# Payload_PC104.net
KiCad netlist of a schematic drawn in Altium Designer
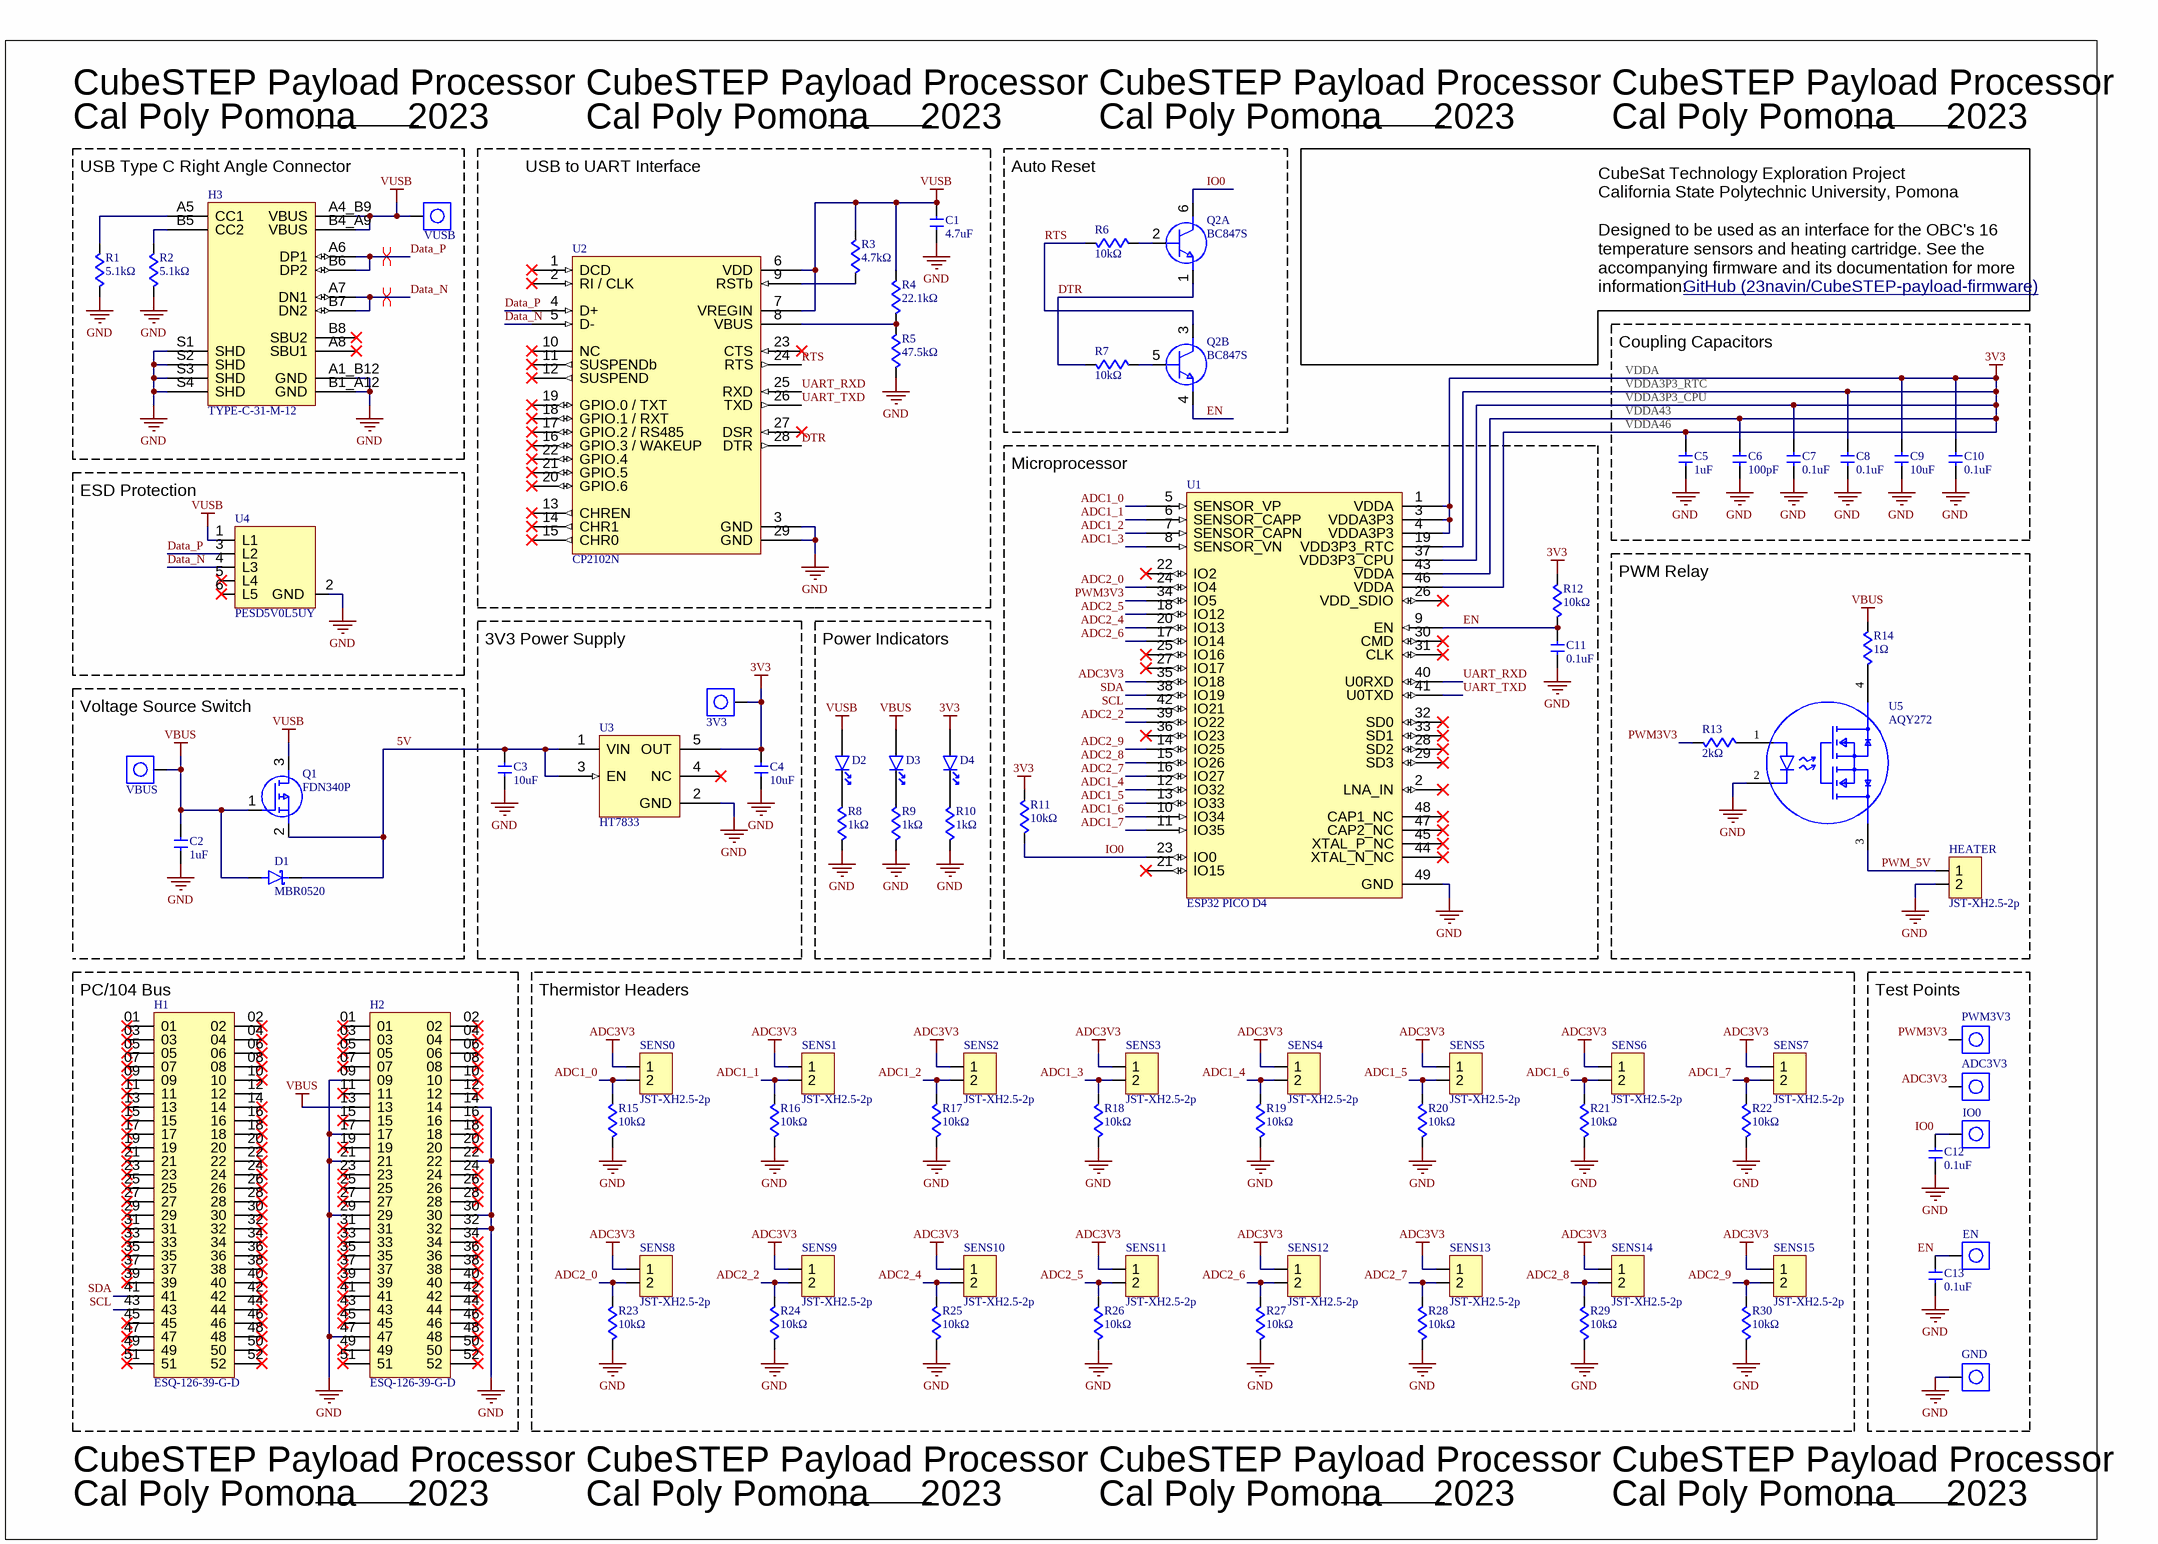
[diagram p0: Payload PC104.SchDoc]

(export (version "E")
  (design (tool "Eeschema 10.0.6"))
  (components
    (comp (ref "3V3")
      (value "Test Point")
      (footprint "Test Point-Footprint-1")
      (description "Signal test point")
      (libsource (lib "CubeSTEP Payload") (part "Test Point-Symbol-1"))
    )
    (comp (ref "ADC3V3")
      (value "Test Point")
      (footprint "Test Point-Footprint-1")
      (description "Signal test point")
      (libsource (lib "CubeSTEP Payload") (part "Test Point-Symbol-1"))
    )
    (comp (ref "C1")
      (value "4.7uF")
      (footprint "0402_Capacitor")
      (description "±20% 16V X5R SMD 0402")
      (fields (field (name "PART NUMBER") "CM05X5R475M16AH") (field (name "MANUFACTURER") "--"))
      (libsource (lib "CubeSTEP Payload") (part "Capacitor"))
    )
    (comp (ref "C2")
      (value "1uF")
      (footprint "0402_Capacitor")
      (description "±10% 16V X5R SMD 0402")
      (fields (field (name "PART NUMBER") "GRM155R61C105KA12D") (field (name "JLCPCB PART #") "C77006"))
      (libsource (lib "CubeSTEP Payload") (part "Capacitor"))
    )
    (comp (ref "C3")
      (value "10uF")
      (footprint "0805_Capacitor_Murata")
      (description "±10% 16V B SMD 0805")
      (fields (field (name "PART NUMBER") "GRM21BB31C106KE15L") (field (name "JLCPCB PART #") "C162317"))
      (libsource (lib "CubeSTEP Payload") (part "Capacitor"))
    )
    (comp (ref "C4")
      (value "10uF")
      (footprint "0805_Capacitor_Murata")
      (description "±10% 16V B SMD 0805")
      (fields (field (name "PART NUMBER") "GRM21BB31C106KE15L") (field (name "JLCPCB PART #") "C162317"))
      (libsource (lib "CubeSTEP Payload") (part "Capacitor"))
    )
    (comp (ref "C5")
      (value "1uF")
      (footprint "0402_Capacitor")
      (description "±10% 16V X5R SMD 0402")
      (fields (field (name "PART NUMBER") "GRM155R61C105KA12D") (field (name "JLCPCB PART #") "C77006"))
      (libsource (lib "CubeSTEP Payload") (part "Capacitor"))
    )
    (comp (ref "C6")
      (value "100pF")
      (footprint "0402_Capacitor")
      (description "±10% 16V X5R SMD 0402")
      (fields (field (name "MANUFACTURER") "YAGEO") (field (name "TOLERANCE") "±10%"))
      (libsource (lib "CubeSTEP Payload") (part "Capacitor"))
    )
    (comp (ref "C7")
      (value "0.1uF")
      (footprint "0402_Capacitor")
      (description "±20% 16V X5R SMD 0402")
      (fields (field (name "PART NUMBER") "TCC0402X5R104M160AT") (field (name "TOLERANCE") "±20%"))
      (libsource (lib "CubeSTEP Payload") (part "Capacitor"))
    )
    (comp (ref "C8")
      (value "0.1uF")
      (footprint "0402_Capacitor")
      (description "±20% 16V X5R SMD 0402")
      (fields (field (name "PART NUMBER") "TCC0402X5R104M160AT") (field (name "TOLERANCE") "±20%"))
      (libsource (lib "CubeSTEP Payload") (part "Capacitor"))
    )
    (comp (ref "C9")
      (value "10uF")
      (footprint "0805_Capacitor_Murata")
      (description "±10% 16V B SMD 0805")
      (fields (field (name "PART NUMBER") "GRM21BB31C106KE15L") (field (name "JLCPCB PART #") "C162317"))
      (libsource (lib "CubeSTEP Payload") (part "Capacitor"))
    )
    (comp (ref "C10")
      (value "0.1uF")
      (footprint "0402_Capacitor")
      (description "±20% 16V X5R SMD 0402")
      (fields (field (name "PART NUMBER") "TCC0402X5R104M160AT") (field (name "TOLERANCE") "±20%"))
      (libsource (lib "CubeSTEP Payload") (part "Capacitor"))
    )
    (comp (ref "C11")
      (value "0.1uF")
      (footprint "0402_Capacitor")
      (description "±20% 16V X5R SMD 0402")
      (fields (field (name "PART NUMBER") "TCC0402X5R104M160AT") (field (name "TOLERANCE") "±20%"))
      (libsource (lib "CubeSTEP Payload") (part "Capacitor"))
    )
    (comp (ref "C12")
      (value "0.1uF")
      (footprint "0402_Capacitor")
      (description "±20% 16V X5R SMD 0402")
      (fields (field (name "PART NUMBER") "TCC0402X5R104M160AT") (field (name "TOLERANCE") "±20%"))
      (libsource (lib "CubeSTEP Payload") (part "Capacitor"))
    )
    (comp (ref "C13")
      (value "0.1uF")
      (footprint "0402_Capacitor")
      (description "±20% 16V X5R SMD 0402")
      (fields (field (name "PART NUMBER") "TCC0402X5R104M160AT") (field (name "TOLERANCE") "±20%"))
      (libsource (lib "CubeSTEP Payload") (part "Capacitor"))
    )
    (comp (ref "D1")
      (value "MBR0520")
      (footprint "SOD-123_Diode_Onsemi")
      (description "Rectifier Diode, Schottky, 1 Phase, 1 Element, 0.5A, 20V V(RRM), Silicon")
      (fields (field (name "JLCPCB PART #") "C475717"))
      (libsource (lib "CubeSTEP Payload") (part "Schottky Diodde"))
    )
    (comp (ref "D2")
      (value "NCD0603R2")
      (footprint "0603_LED")
      (fields (field (name "JLCPCB PART #") "C90692"))
      (libsource (lib "CubeSTEP Payload") (part "LED"))
    )
    (comp (ref "D3")
      (value "NCD0603R2")
      (footprint "0603_LED")
      (fields (field (name "JLCPCB PART #") "C90692"))
      (libsource (lib "CubeSTEP Payload") (part "LED"))
    )
    (comp (ref "D4")
      (value "NCD0603R2")
      (footprint "0603_LED")
      (fields (field (name "JLCPCB PART #") "C90692"))
      (libsource (lib "CubeSTEP Payload") (part "LED"))
    )
    (comp (ref "EN")
      (value "Test Point")
      (footprint "Test Point-Footprint-1")
      (description "Signal test point")
      (libsource (lib "CubeSTEP Payload") (part "Test Point-Symbol-1"))
    )
    (comp (ref "GND")
      (value "Test Point")
      (footprint "Test Point-Footprint-1")
      (description "Signal test point")
      (libsource (lib "CubeSTEP Payload") (part "Test Point-Symbol-1"))
    )
    (comp (ref "H1")
      (value "ESQ-126-39-G-D")
      (footprint "ESQ-126-39-G-D")
      (libsource (lib "CubeSTEP Payload") (part "ESQ-126-39-G-D"))
    )
    (comp (ref "H2")
      (value "ESQ-126-39-G-D")
      (footprint "ESQ-126-39-G-D")
      (libsource (lib "CubeSTEP Payload") (part "ESQ-126-39-G-D"))
    )
    (comp (ref "H3")
      (value "TYPE-C-31-M-12")
      (footprint "TYPE-C-31-M-12-Footprint-1")
      (description "5A 1 16P Female Type-C SMD USB Connectors ROHS")
      (fields (field (name "JLCPCB PART #") "C165948"))
      (libsource (lib "CubeSTEP Payload") (part "TYPE-C-31-M-12-Symbol-1"))
    )
    (comp (ref "HEATER")
      (value "JST-XH2.5-2p")
      (footprint "2.5_2p_Header")
      (description "1x2P XH 1 2.5mm 2 Brass Push-Pull,P=2.5mm Wire To Board / Wire To Wire Connector ROHS")
      (fields
        (field (name "MANUFACTURER") "Ckmtw(Shenzhen Cankemeng)")
        (field (name "JLCPCB PART #") "C132479")
      )
      (libsource (lib "CubeSTEP Payload") (part "JST-XH2.5-2p"))
    )
    (comp (ref "IO0")
      (value "Test Point")
      (footprint "Test Point-Footprint-1")
      (description "Signal test point")
      (libsource (lib "CubeSTEP Payload") (part "Test Point-Symbol-1"))
    )
    (comp (ref "PWM3V3")
      (value "Test Point")
      (footprint "Test Point-Footprint-1")
      (description "Signal test point")
      (libsource (lib "CubeSTEP Payload") (part "Test Point-Symbol-1"))
    )
    (comp (ref "Q1")
      (value "FDN340P")
      (footprint "SOT-23")
      (description "SOT-23 MOSFETs ROHS")
      (fields (field (name "JLCPCB PART #") "C347510"))
      (libsource (lib "CubeSTEP Payload") (part "FDN340P"))
    )
    (comp (ref "Q2")
      (value "BC847S")
      (footprint "SC-70-6(SOT-363)")
      (description "Small Signal Bipolar Transistor, 0.1A I(C), 45V V(BR)CEO, 2-Element, NPN, Silicon")
      (fields (field (name "JLCPCB PART #") "C148112"))
      (libsource (lib "CubeSTEP Payload") (part "BC847S"))
    )
    (comp (ref "R1")
      (value "5.1kΩ")
      (footprint "0402_Resistor")
      (description "±0.5% 62.5mW 50V SMD 0402")
      (fields (field (name "POWER") "62.5mW") (field (name "PART NUMBER") "0402WGD5101TCE"))
      (libsource (lib "CubeSTEP Payload") (part "Resistor"))
    )
    (comp (ref "R2")
      (value "5.1kΩ")
      (footprint "0402_Resistor")
      (description "±0.5% 62.5mW 50V SMD 0402")
      (fields (field (name "POWER") "62.5mW") (field (name "PART NUMBER") "0402WGD5101TCE"))
      (libsource (lib "CubeSTEP Payload") (part "Resistor"))
    )
    (comp (ref "R3")
      (value "4.7kΩ")
      (footprint "0402_Resistor")
      (description "±1% 62.5mW 50V SMD 0402")
      (fields (field (name "PART NUMBER") "RC0402FR-074K7L") (field (name "POWER") "62.5mW"))
      (libsource (lib "CubeSTEP Payload") (part "Resistor"))
    )
    (comp (ref "R4")
      (value "22.1kΩ")
      (footprint "0402_Resistor")
      (description "±1% 62.5mW50V SMD 0402")
      (fields (field (name "POWER") "62.5mW") (field (name "PART NUMBER") "RC0402FR-0722K1L"))
      (libsource (lib "CubeSTEP Payload") (part "Resistor"))
    )
    (comp (ref "R5")
      (value "47.5kΩ")
      (footprint "0402_Resistor")
      (description "±1% 62.5mW 50V SMD 0402")
      (fields (field (name "PART NUMBER") "RC0402FR-0747K5L") (field (name "POWER") "62.5mW"))
      (libsource (lib "CubeSTEP Payload") (part "Resistor"))
    )
    (comp (ref "R6")
      (value "10kΩ")
      (footprint "0402_Resistor")
      (description "±1% 62.5mW 50V SMD 0402")
      (fields (field (name "POWER") "62.5mW") (field (name "TOLERANCE") "±1%"))
      (libsource (lib "CubeSTEP Payload") (part "Resistor"))
    )
    (comp (ref "R7")
      (value "10kΩ")
      (footprint "0402_Resistor")
      (description "±1% 62.5mW 50V SMD 0402")
      (fields (field (name "POWER") "62.5mW") (field (name "TOLERANCE") "±1%"))
      (libsource (lib "CubeSTEP Payload") (part "Resistor"))
    )
    (comp (ref "R8")
      (value "1kΩ")
      (footprint "0402_Resistor")
      (description "±1% 62.5mW 50V SMD 0402")
      (fields (field (name "JLCPCB PART #") "C106235") (field (name "TOLERANCE") "±1%"))
      (libsource (lib "CubeSTEP Payload") (part "Resistor"))
    )
    (comp (ref "R9")
      (value "1kΩ")
      (footprint "0402_Resistor")
      (description "±1% 62.5mW 50V SMD 0402")
      (fields (field (name "JLCPCB PART #") "C106235") (field (name "TOLERANCE") "±1%"))
      (libsource (lib "CubeSTEP Payload") (part "Resistor"))
    )
    (comp (ref "R10")
      (value "1kΩ")
      (footprint "0402_Resistor")
      (description "±1% 62.5mW 50V SMD 0402")
      (fields (field (name "JLCPCB PART #") "C106235") (field (name "TOLERANCE") "±1%"))
      (libsource (lib "CubeSTEP Payload") (part "Resistor"))
    )
    (comp (ref "R11")
      (value "10kΩ")
      (footprint "0402_Resistor")
      (description "±1% 62.5mW 50V SMD 0402")
      (fields (field (name "POWER") "62.5mW") (field (name "TOLERANCE") "±1%"))
      (libsource (lib "CubeSTEP Payload") (part "Resistor"))
    )
    (comp (ref "R12")
      (value "10kΩ")
      (footprint "0402_Resistor")
      (description "±1% 62.5mW 50V SMD 0402")
      (fields (field (name "POWER") "62.5mW") (field (name "TOLERANCE") "±1%"))
      (libsource (lib "CubeSTEP Payload") (part "Resistor"))
    )
    (comp (ref "R13")
      (value "2kΩ")
      (footprint "0402_Resistor")
      (description "±1% 62.5mW 50V SMD 0402")
      (fields (field (name "TOLERANCE") "±1%") (field (name "JLCPCB PART #") "C100291"))
      (libsource (lib "CubeSTEP Payload") (part "Resistor"))
    )
    (comp (ref "R14")
      (value "1Ω")
      (footprint "2010_Resistor")
      (description "±5% 0.75W 200V SMD 2010")
      (fields (field (name "POWER") "750mW") (field (name "TOLERANCE") "±5%"))
      (libsource (lib "CubeSTEP Payload") (part "Resistor"))
    )
    (comp (ref "R15")
      (value "10kΩ")
      (footprint "0402_Resistor")
      (description "±1% 62.5mW 50V SMD 0402")
      (fields (field (name "POWER") "62.5mW") (field (name "TOLERANCE") "±1%"))
      (libsource (lib "CubeSTEP Payload") (part "Resistor"))
    )
    (comp (ref "R16")
      (value "10kΩ")
      (footprint "0402_Resistor")
      (description "±1% 62.5mW 50V SMD 0402")
      (fields (field (name "POWER") "62.5mW") (field (name "TOLERANCE") "±1%"))
      (libsource (lib "CubeSTEP Payload") (part "Resistor"))
    )
    (comp (ref "R17")
      (value "10kΩ")
      (footprint "0402_Resistor")
      (description "±1% 62.5mW 50V SMD 0402")
      (fields (field (name "POWER") "62.5mW") (field (name "TOLERANCE") "±1%"))
      (libsource (lib "CubeSTEP Payload") (part "Resistor"))
    )
    (comp (ref "R18")
      (value "10kΩ")
      (footprint "0402_Resistor")
      (description "±1% 62.5mW 50V SMD 0402")
      (fields (field (name "POWER") "62.5mW") (field (name "TOLERANCE") "±1%"))
      (libsource (lib "CubeSTEP Payload") (part "Resistor"))
    )
    (comp (ref "R19")
      (value "10kΩ")
      (footprint "0402_Resistor")
      (description "±1% 62.5mW 50V SMD 0402")
      (fields (field (name "POWER") "62.5mW") (field (name "TOLERANCE") "±1%"))
      (libsource (lib "CubeSTEP Payload") (part "Resistor"))
    )
    (comp (ref "R20")
      (value "10kΩ")
      (footprint "0402_Resistor")
      (description "±1% 62.5mW 50V SMD 0402")
      (fields (field (name "POWER") "62.5mW") (field (name "TOLERANCE") "±1%"))
      (libsource (lib "CubeSTEP Payload") (part "Resistor"))
    )
    (comp (ref "R21")
      (value "10kΩ")
      (footprint "0402_Resistor")
      (description "±1% 62.5mW 50V SMD 0402")
      (fields (field (name "POWER") "62.5mW") (field (name "TOLERANCE") "±1%"))
      (libsource (lib "CubeSTEP Payload") (part "Resistor"))
    )
    (comp (ref "R22")
      (value "10kΩ")
      (footprint "0402_Resistor")
      (description "±1% 62.5mW 50V SMD 0402")
      (fields (field (name "POWER") "62.5mW") (field (name "TOLERANCE") "±1%"))
      (libsource (lib "CubeSTEP Payload") (part "Resistor"))
    )
    (comp (ref "R23")
      (value "10kΩ")
      (footprint "0402_Resistor")
      (description "±1% 62.5mW 50V SMD 0402")
      (fields (field (name "POWER") "62.5mW") (field (name "TOLERANCE") "±1%"))
      (libsource (lib "CubeSTEP Payload") (part "Resistor"))
    )
    (comp (ref "R24")
      (value "10kΩ")
      (footprint "0402_Resistor")
      (description "±1% 62.5mW 50V SMD 0402")
      (fields (field (name "POWER") "62.5mW") (field (name "TOLERANCE") "±1%"))
      (libsource (lib "CubeSTEP Payload") (part "Resistor"))
    )
    (comp (ref "R25")
      (value "10kΩ")
      (footprint "0402_Resistor")
      (description "±1% 62.5mW 50V SMD 0402")
      (fields (field (name "POWER") "62.5mW") (field (name "TOLERANCE") "±1%"))
      (libsource (lib "CubeSTEP Payload") (part "Resistor"))
    )
    (comp (ref "R26")
      (value "10kΩ")
      (footprint "0402_Resistor")
      (description "±1% 62.5mW 50V SMD 0402")
      (fields (field (name "POWER") "62.5mW") (field (name "TOLERANCE") "±1%"))
      (libsource (lib "CubeSTEP Payload") (part "Resistor"))
    )
    (comp (ref "R27")
      (value "10kΩ")
      (footprint "0402_Resistor")
      (description "±1% 62.5mW 50V SMD 0402")
      (fields (field (name "POWER") "62.5mW") (field (name "TOLERANCE") "±1%"))
      (libsource (lib "CubeSTEP Payload") (part "Resistor"))
    )
    (comp (ref "R28")
      (value "10kΩ")
      (footprint "0402_Resistor")
      (description "±1% 62.5mW 50V SMD 0402")
      (fields (field (name "POWER") "62.5mW") (field (name "TOLERANCE") "±1%"))
      (libsource (lib "CubeSTEP Payload") (part "Resistor"))
    )
    (comp (ref "R29")
      (value "10kΩ")
      (footprint "0402_Resistor")
      (description "±1% 62.5mW 50V SMD 0402")
      (fields (field (name "POWER") "62.5mW") (field (name "TOLERANCE") "±1%"))
      (libsource (lib "CubeSTEP Payload") (part "Resistor"))
    )
    (comp (ref "R30")
      (value "10kΩ")
      (footprint "0402_Resistor")
      (description "±1% 62.5mW 50V SMD 0402")
      (fields (field (name "POWER") "62.5mW") (field (name "TOLERANCE") "±1%"))
      (libsource (lib "CubeSTEP Payload") (part "Resistor"))
    )
    (comp (ref "SENS0")
      (value "JST-XH2.5-2p")
      (footprint "2.5_2p_Header")
      (description "1x2P XH 1 2.5mm 2 Brass Push-Pull,P=2.5mm Wire To Board / Wire To Wire Connector ROHS")
      (fields
        (field (name "MANUFACTURER") "Ckmtw(Shenzhen Cankemeng)")
        (field (name "JLCPCB PART #") "C132479")
      )
      (libsource (lib "CubeSTEP Payload") (part "JST-XH2.5-2p"))
    )
    (comp (ref "SENS1")
      (value "JST-XH2.5-2p")
      (footprint "2.5_2p_Header")
      (description "1x2P XH 1 2.5mm 2 Brass Push-Pull,P=2.5mm Wire To Board / Wire To Wire Connector ROHS")
      (fields
        (field (name "MANUFACTURER") "Ckmtw(Shenzhen Cankemeng)")
        (field (name "JLCPCB PART #") "C132479")
      )
      (libsource (lib "CubeSTEP Payload") (part "JST-XH2.5-2p"))
    )
    (comp (ref "SENS2")
      (value "JST-XH2.5-2p")
      (footprint "2.5_2p_Header")
      (description "1x2P XH 1 2.5mm 2 Brass Push-Pull,P=2.5mm Wire To Board / Wire To Wire Connector ROHS")
      (fields
        (field (name "MANUFACTURER") "Ckmtw(Shenzhen Cankemeng)")
        (field (name "JLCPCB PART #") "C132479")
      )
      (libsource (lib "CubeSTEP Payload") (part "JST-XH2.5-2p"))
    )
    (comp (ref "SENS3")
      (value "JST-XH2.5-2p")
      (footprint "2.5_2p_Header")
      (description "1x2P XH 1 2.5mm 2 Brass Push-Pull,P=2.5mm Wire To Board / Wire To Wire Connector ROHS")
      (fields
        (field (name "MANUFACTURER") "Ckmtw(Shenzhen Cankemeng)")
        (field (name "JLCPCB PART #") "C132479")
      )
      (libsource (lib "CubeSTEP Payload") (part "JST-XH2.5-2p"))
    )
    (comp (ref "SENS4")
      (value "JST-XH2.5-2p")
      (footprint "2.5_2p_Header")
      (description "1x2P XH 1 2.5mm 2 Brass Push-Pull,P=2.5mm Wire To Board / Wire To Wire Connector ROHS")
      (fields
        (field (name "MANUFACTURER") "Ckmtw(Shenzhen Cankemeng)")
        (field (name "JLCPCB PART #") "C132479")
      )
      (libsource (lib "CubeSTEP Payload") (part "JST-XH2.5-2p"))
    )
    (comp (ref "SENS5")
      (value "JST-XH2.5-2p")
      (footprint "2.5_2p_Header")
      (description "1x2P XH 1 2.5mm 2 Brass Push-Pull,P=2.5mm Wire To Board / Wire To Wire Connector ROHS")
      (fields
        (field (name "MANUFACTURER") "Ckmtw(Shenzhen Cankemeng)")
        (field (name "JLCPCB PART #") "C132479")
      )
      (libsource (lib "CubeSTEP Payload") (part "JST-XH2.5-2p"))
    )
    (comp (ref "SENS6")
      (value "JST-XH2.5-2p")
      (footprint "2.5_2p_Header")
      (description "1x2P XH 1 2.5mm 2 Brass Push-Pull,P=2.5mm Wire To Board / Wire To Wire Connector ROHS")
      (fields
        (field (name "MANUFACTURER") "Ckmtw(Shenzhen Cankemeng)")
        (field (name "JLCPCB PART #") "C132479")
      )
      (libsource (lib "CubeSTEP Payload") (part "JST-XH2.5-2p"))
    )
    (comp (ref "SENS7")
      (value "JST-XH2.5-2p")
      (footprint "2.5_2p_Header")
      (description "1x2P XH 1 2.5mm 2 Brass Push-Pull,P=2.5mm Wire To Board / Wire To Wire Connector ROHS")
      (fields
        (field (name "MANUFACTURER") "Ckmtw(Shenzhen Cankemeng)")
        (field (name "JLCPCB PART #") "C132479")
      )
      (libsource (lib "CubeSTEP Payload") (part "JST-XH2.5-2p"))
    )
    (comp (ref "SENS8")
      (value "JST-XH2.5-2p")
      (footprint "2.5_2p_Header")
      (description "1x2P XH 1 2.5mm 2 Brass Push-Pull,P=2.5mm Wire To Board / Wire To Wire Connector ROHS")
      (fields
        (field (name "MANUFACTURER") "Ckmtw(Shenzhen Cankemeng)")
        (field (name "JLCPCB PART #") "C132479")
      )
      (libsource (lib "CubeSTEP Payload") (part "JST-XH2.5-2p"))
    )
    (comp (ref "SENS9")
      (value "JST-XH2.5-2p")
      (footprint "2.5_2p_Header")
      (description "1x2P XH 1 2.5mm 2 Brass Push-Pull,P=2.5mm Wire To Board / Wire To Wire Connector ROHS")
      (fields
        (field (name "MANUFACTURER") "Ckmtw(Shenzhen Cankemeng)")
        (field (name "JLCPCB PART #") "C132479")
      )
      (libsource (lib "CubeSTEP Payload") (part "JST-XH2.5-2p"))
    )
    (comp (ref "SENS10")
      (value "JST-XH2.5-2p")
      (footprint "2.5_2p_Header")
      (description "1x2P XH 1 2.5mm 2 Brass Push-Pull,P=2.5mm Wire To Board / Wire To Wire Connector ROHS")
      (fields
        (field (name "MANUFACTURER") "Ckmtw(Shenzhen Cankemeng)")
        (field (name "JLCPCB PART #") "C132479")
      )
      (libsource (lib "CubeSTEP Payload") (part "JST-XH2.5-2p"))
    )
    (comp (ref "SENS11")
      (value "JST-XH2.5-2p")
      (footprint "2.5_2p_Header")
      (description "1x2P XH 1 2.5mm 2 Brass Push-Pull,P=2.5mm Wire To Board / Wire To Wire Connector ROHS")
      (fields
        (field (name "MANUFACTURER") "Ckmtw(Shenzhen Cankemeng)")
        (field (name "JLCPCB PART #") "C132479")
      )
      (libsource (lib "CubeSTEP Payload") (part "JST-XH2.5-2p"))
    )
    (comp (ref "SENS12")
      (value "JST-XH2.5-2p")
      (footprint "2.5_2p_Header")
      (description "1x2P XH 1 2.5mm 2 Brass Push-Pull,P=2.5mm Wire To Board / Wire To Wire Connector ROHS")
      (fields
        (field (name "MANUFACTURER") "Ckmtw(Shenzhen Cankemeng)")
        (field (name "JLCPCB PART #") "C132479")
      )
      (libsource (lib "CubeSTEP Payload") (part "JST-XH2.5-2p"))
    )
    (comp (ref "SENS13")
      (value "JST-XH2.5-2p")
      (footprint "2.5_2p_Header")
      (description "1x2P XH 1 2.5mm 2 Brass Push-Pull,P=2.5mm Wire To Board / Wire To Wire Connector ROHS")
      (fields
        (field (name "MANUFACTURER") "Ckmtw(Shenzhen Cankemeng)")
        (field (name "JLCPCB PART #") "C132479")
      )
      (libsource (lib "CubeSTEP Payload") (part "JST-XH2.5-2p"))
    )
    (comp (ref "SENS14")
      (value "JST-XH2.5-2p")
      (footprint "2.5_2p_Header")
      (description "1x2P XH 1 2.5mm 2 Brass Push-Pull,P=2.5mm Wire To Board / Wire To Wire Connector ROHS")
      (fields
        (field (name "MANUFACTURER") "Ckmtw(Shenzhen Cankemeng)")
        (field (name "JLCPCB PART #") "C132479")
      )
      (libsource (lib "CubeSTEP Payload") (part "JST-XH2.5-2p"))
    )
    (comp (ref "SENS15")
      (value "JST-XH2.5-2p")
      (footprint "2.5_2p_Header")
      (description "1x2P XH 1 2.5mm 2 Brass Push-Pull,P=2.5mm Wire To Board / Wire To Wire Connector ROHS")
      (fields
        (field (name "MANUFACTURER") "Ckmtw(Shenzhen Cankemeng)")
        (field (name "JLCPCB PART #") "C132479")
      )
      (libsource (lib "CubeSTEP Payload") (part "JST-XH2.5-2p"))
    )
    (comp (ref "U1")
      (value "ESP32 PICO D4")
      (footprint "QFN-48-EP(7x7)")
      (description "System-on-Chip integrating an ESP32 chip together with a 4 MB SPI flash")
      (fields (field (name "JLCPCB PART #") "C193707") (field (name "PART NUMBER") "ESP32-PICO-D4"))
      (libsource (lib "CubeSTEP Payload") (part "ESP32 PICO D4"))
    )
    (comp (ref "U2")
      (value "CP2102N")
      (footprint "QFN-28-EP(5x5)")
      (description "USB-to-UART bridge controller")
      (fields (field (name "JLCPCB PART #") "C964632") (field (name "PART NUMBER") "CP2102N-A02-GQFN28R"))
      (libsource (lib "CubeSTEP Payload") (part "CP2102N-A02-GQFN28R"))
    )
    (comp (ref "U3")
      (value "HT7833")
      (footprint "SOT-23-5")
      (description "SOT-23-5 Linear Voltage Regulators (LDO) ROHS")
      (fields (field (name "MANUFACTURER") "TECH PUBLIC") (field (name "JLCPCB PART #") "C3011187"))
      (libsource (lib "CubeSTEP Payload") (part "HT7833"))
    )
    (comp (ref "U4")
      (value "PESD5V0L5UY")
      (footprint "SOT-363")
      (description "Trans Voltage Suppressor Diode, 25W, 5V V(RWM), Unidirectional, 5 Element, Silicon")
      (fields
        (field (name "JLCPCB PART #") "C2831528")
        (field (name "MANUFACTURER") "UMW(Youtai Semiconductor Co., Ltd.)")
      )
      (libsource (lib "CubeSTEP Payload") (part "PESD5V0L5UY"))
    )
    (comp (ref "U5")
      (value "AQY272")
      (footprint "DIP4_AQY272_Panasonic")
      (description "Solid State Relays 1.25V 60V 0.11Ω 2A AC,DC DIP-4 - MOS Output (PhotoMOS) ROHS 1 Form A(SPST-NO)")
      (fields (field (name "JLCPCB PART #") "C62652"))
      (libsource (lib "CubeSTEP Payload") (part "AQY272"))
    )
    (comp (ref "VBUS")
      (value "Test Point")
      (footprint "Test Point-Footprint-1")
      (description "Signal test point")
      (libsource (lib "CubeSTEP Payload") (part "Test Point-Symbol-1"))
    )
    (comp (ref "VUSB")
      (value "Test Point")
      (footprint "Test Point-Footprint-1")
      (description "Signal test point")
      (libsource (lib "CubeSTEP Payload") (part "Test Point-Symbol-1"))
    )
  )
  (nets
    (net (code "1") (name "/5V") (class "Default")
      (node (ref "C3") (pin "1") (pinfunction "1_1") (pintype "passive"))
      (node (ref "D1") (pin "1") (pinfunction "Cathode_1") (pintype "passive"))
      (node (ref "Q1") (pin "2") (pinfunction "S_2") (pintype "passive"))
      (node (ref "U3") (pin "1") (pinfunction "VIN_1") (pintype "power_in"))
      (node (ref "U3") (pin "3") (pinfunction "EN_3") (pintype "input"))
    )
    (net (code "2") (name "/ADC1_0") (class "Default")
      (node (ref "R15") (pin "2") (pinfunction "2_2") (pintype "passive"))
      (node (ref "SENS0") (pin "2") (pinfunction "2_2") (pintype "passive"))
      (node (ref "U1") (pin "5") (pinfunction "SENSOR_VP_5") (pintype "input"))
    )
    (net (code "3") (name "/ADC1_1") (class "Default")
      (node (ref "R16") (pin "2") (pinfunction "2_2") (pintype "passive"))
      (node (ref "SENS1") (pin "2") (pinfunction "2_2") (pintype "passive"))
      (node (ref "U1") (pin "6") (pinfunction "SENSOR_CAPP_6") (pintype "input"))
    )
    (net (code "4") (name "/ADC1_2") (class "Default")
      (node (ref "R17") (pin "2") (pinfunction "2_2") (pintype "passive"))
      (node (ref "SENS2") (pin "2") (pinfunction "2_2") (pintype "passive"))
      (node (ref "U1") (pin "7") (pinfunction "SENSOR_CAPN_7") (pintype "input"))
    )
    (net (code "5") (name "/ADC1_3") (class "Default")
      (node (ref "R18") (pin "2") (pinfunction "2_2") (pintype "passive"))
      (node (ref "SENS3") (pin "2") (pinfunction "2_2") (pintype "passive"))
      (node (ref "U1") (pin "8") (pinfunction "SENSOR_VN_8") (pintype "input"))
    )
    (net (code "6") (name "/ADC1_4") (class "Default")
      (node (ref "R19") (pin "2") (pinfunction "2_2") (pintype "passive"))
      (node (ref "SENS4") (pin "2") (pinfunction "2_2") (pintype "passive"))
      (node (ref "U1") (pin "12") (pinfunction "IO32_12") (pintype "bidirectional"))
    )
    (net (code "7") (name "/ADC1_5") (class "Default")
      (node (ref "R20") (pin "2") (pinfunction "2_2") (pintype "passive"))
      (node (ref "SENS5") (pin "2") (pinfunction "2_2") (pintype "passive"))
      (node (ref "U1") (pin "13") (pinfunction "IO33_13") (pintype "bidirectional"))
    )
    (net (code "8") (name "/ADC1_6") (class "Default")
      (node (ref "R21") (pin "2") (pinfunction "2_2") (pintype "passive"))
      (node (ref "SENS6") (pin "2") (pinfunction "2_2") (pintype "passive"))
      (node (ref "U1") (pin "10") (pinfunction "IO34_10") (pintype "input"))
    )
    (net (code "9") (name "/ADC1_7") (class "Default")
      (node (ref "R22") (pin "2") (pinfunction "2_2") (pintype "passive"))
      (node (ref "SENS7") (pin "2") (pinfunction "2_2") (pintype "passive"))
      (node (ref "U1") (pin "11") (pinfunction "IO35_11") (pintype "input"))
    )
    (net (code "10") (name "/ADC2_0") (class "Default")
      (node (ref "R23") (pin "2") (pinfunction "2_2") (pintype "passive"))
      (node (ref "SENS8") (pin "2") (pinfunction "2_2") (pintype "passive"))
      (node (ref "U1") (pin "24") (pinfunction "IO4_24") (pintype "bidirectional"))
    )
    (net (code "11") (name "/ADC2_2") (class "Default")
      (node (ref "R24") (pin "2") (pinfunction "2_2") (pintype "passive"))
      (node (ref "SENS9") (pin "2") (pinfunction "2_2") (pintype "passive"))
      (node (ref "U1") (pin "39") (pinfunction "IO22_39") (pintype "bidirectional"))
    )
    (net (code "12") (name "/ADC2_4") (class "Default")
      (node (ref "R25") (pin "2") (pinfunction "2_2") (pintype "passive"))
      (node (ref "SENS10") (pin "2") (pinfunction "2_2") (pintype "passive"))
      (node (ref "U1") (pin "20") (pinfunction "IO13_20") (pintype "bidirectional"))
    )
    (net (code "13") (name "/ADC2_5") (class "Default")
      (node (ref "R26") (pin "2") (pinfunction "2_2") (pintype "passive"))
      (node (ref "SENS11") (pin "2") (pinfunction "2_2") (pintype "passive"))
      (node (ref "U1") (pin "18") (pinfunction "IO12_18") (pintype "bidirectional"))
    )
    (net (code "14") (name "/ADC2_6") (class "Default")
      (node (ref "R27") (pin "2") (pinfunction "2_2") (pintype "passive"))
      (node (ref "SENS12") (pin "2") (pinfunction "2_2") (pintype "passive"))
      (node (ref "U1") (pin "17") (pinfunction "IO14_17") (pintype "bidirectional"))
    )
    (net (code "15") (name "/ADC2_7") (class "Default")
      (node (ref "R28") (pin "2") (pinfunction "2_2") (pintype "passive"))
      (node (ref "SENS13") (pin "2") (pinfunction "2_2") (pintype "passive"))
      (node (ref "U1") (pin "16") (pinfunction "IO27_16") (pintype "bidirectional"))
    )
    (net (code "16") (name "/ADC2_8") (class "Default")
      (node (ref "R29") (pin "2") (pinfunction "2_2") (pintype "passive"))
      (node (ref "SENS14") (pin "2") (pinfunction "2_2") (pintype "passive"))
      (node (ref "U1") (pin "15") (pinfunction "IO26_15") (pintype "bidirectional"))
    )
    (net (code "17") (name "/ADC2_9") (class "Default")
      (node (ref "R30") (pin "2") (pinfunction "2_2") (pintype "passive"))
      (node (ref "SENS15") (pin "2") (pinfunction "2_2") (pintype "passive"))
      (node (ref "U1") (pin "14") (pinfunction "IO25_14") (pintype "bidirectional"))
    )
    (net (code "18") (name "/DTR") (class "Default")
      (node (ref "Q2") (pin "1") (pinfunction "S_1") (pintype "passive"))
      (node (ref "R7") (pin "1") (pinfunction "1_1") (pintype "passive"))
      (node (ref "U2") (pin "28") (pinfunction "DTR_28") (pintype "output"))
    )
    (net (code "19") (name "/Data_N") (class "Default")
      (node (ref "H3") (pin "A7") (pinfunction "DN1_A7") (pintype "bidirectional"))
      (node (ref "H3") (pin "B7") (pinfunction "DN2_B7") (pintype "bidirectional"))
      (node (ref "U2") (pin "5") (pinfunction "D-_5") (pintype "input"))
      (node (ref "U4") (pin "4") (pinfunction "L3_4") (pintype "passive"))
    )
    (net (code "20") (name "/Data_P") (class "Default")
      (node (ref "H3") (pin "A6") (pinfunction "DP1_A6") (pintype "bidirectional"))
      (node (ref "H3") (pin "B6") (pinfunction "DP2_B6") (pintype "bidirectional"))
      (node (ref "U2") (pin "4") (pinfunction "D+_4") (pintype "input"))
      (node (ref "U4") (pin "3") (pinfunction "L2_3") (pintype "passive"))
    )
    (net (code "21") (name "/EN") (class "Default")
      (node (ref "C11") (pin "1") (pinfunction "1_1") (pintype "passive"))
      (node (ref "C13") (pin "2") (pinfunction "2_2") (pintype "passive"))
      (node (ref "EN") (pin "1") (pinfunction "Input_1") (pintype "passive"))
      (node (ref "Q2") (pin "4") (pinfunction "S_4") (pintype "passive"))
      (node (ref "R12") (pin "2") (pinfunction "2_2") (pintype "passive"))
      (node (ref "U1") (pin "9") (pinfunction "EN_9") (pintype "input"))
    )
    (net (code "22") (name "/IO0") (class "Default")
      (node (ref "C12") (pin "2") (pinfunction "2_2") (pintype "passive"))
      (node (ref "IO0") (pin "1") (pinfunction "Input_1") (pintype "passive"))
      (node (ref "Q2") (pin "6") (pinfunction "D_6") (pintype "passive"))
      (node (ref "R11") (pin "2") (pinfunction "2_2") (pintype "passive"))
      (node (ref "U1") (pin "23") (pinfunction "IO0_23") (pintype "bidirectional"))
    )
    (net (code "23") (name "/PWM3V3") (class "Default")
      (node (ref "PWM3V3") (pin "1") (pinfunction "Input_1") (pintype "passive"))
      (node (ref "R13") (pin "1") (pinfunction "1_1") (pintype "passive"))
      (node (ref "U1") (pin "34") (pinfunction "IO5_34") (pintype "bidirectional"))
    )
    (net (code "24") (name "/PWM_5V") (class "Default")
      (node (ref "HEATER") (pin "1") (pinfunction "1_1") (pintype "passive"))
      (node (ref "U5") (pin "3") (pinfunction "1_DRAIN_3") (pintype "passive"))
    )
    (net (code "25") (name "/RTS") (class "Default")
      (node (ref "Q2") (pin "3") (pinfunction "D_3") (pintype "passive"))
      (node (ref "R6") (pin "1") (pinfunction "1_1") (pintype "passive"))
      (node (ref "U2") (pin "24") (pinfunction "RTS_24") (pintype "output"))
    )
    (net (code "26") (name "/SCL") (class "Default")
      (node (ref "H1") (pin "43") (pinfunction "43_43") (pintype "passive"))
      (node (ref "U1") (pin "42") (pinfunction "IO21_42") (pintype "bidirectional"))
    )
    (net (code "27") (name "/SDA") (class "Default")
      (node (ref "H1") (pin "41") (pinfunction "41_41") (pintype "passive"))
      (node (ref "U1") (pin "38") (pinfunction "IO19_38") (pintype "bidirectional"))
    )
    (net (code "28") (name "/UART_RXD") (class "Default")
      (node (ref "U1") (pin "40") (pinfunction "U0RXD_40") (pintype "bidirectional"))
      (node (ref "U2") (pin "25") (pinfunction "RXD_25") (pintype "input"))
    )
    (net (code "29") (name "/UART_TXD") (class "Default")
      (node (ref "U1") (pin "41") (pinfunction "U0TXD_41") (pintype "bidirectional"))
      (node (ref "U2") (pin "26") (pinfunction "TXD_26") (pintype "output"))
    )
    (net (code "30") (name "3V3") (class "Default")
      (node (ref "3V3") (pin "1") (pinfunction "Input_1") (pintype "passive"))
      (node (ref "C10") (pin "2") (pinfunction "2_2") (pintype "passive"))
      (node (ref "C4") (pin "1") (pinfunction "1_1") (pintype "passive"))
      (node (ref "C5") (pin "1") (pinfunction "1_1") (pintype "passive"))
      (node (ref "C6") (pin "1") (pinfunction "1_1") (pintype "passive"))
      (node (ref "C7") (pin "2") (pinfunction "2_2") (pintype "passive"))
      (node (ref "C8") (pin "2") (pinfunction "2_2") (pintype "passive"))
      (node (ref "C9") (pin "1") (pinfunction "1_1") (pintype "passive"))
      (node (ref "D4") (pin "2") (pinfunction "Anode_2") (pintype "passive"))
      (node (ref "R11") (pin "1") (pinfunction "1_1") (pintype "passive"))
      (node (ref "R12") (pin "1") (pinfunction "1_1") (pintype "passive"))
      (node (ref "U1") (pin "1") (pinfunction "VDDA_1") (pintype "power_in"))
      (node (ref "U1") (pin "19") (pinfunction "VDD3P3_RTC_19") (pintype "power_in"))
      (node (ref "U1") (pin "3") (pinfunction "VDDA3P3_3") (pintype "power_in"))
      (node (ref "U1") (pin "37") (pinfunction "VDD3P3_CPU_37") (pintype "power_in"))
      (node (ref "U1") (pin "4") (pinfunction "VDDA3P3_4") (pintype "power_in"))
      (node (ref "U1") (pin "43") (pinfunction "VDDA_43") (pintype "power_in"))
      (node (ref "U1") (pin "46") (pinfunction "VDDA_46") (pintype "power_in"))
      (node (ref "U3") (pin "5") (pinfunction "OUT_5") (pintype "power_in"))
    )
    (net (code "31") (name "ADC3V3") (class "Default")
      (node (ref "ADC3V3") (pin "1") (pinfunction "Input_1") (pintype "passive"))
      (node (ref "SENS0") (pin "1") (pinfunction "1_1") (pintype "passive"))
      (node (ref "SENS1") (pin "1") (pinfunction "1_1") (pintype "passive"))
      (node (ref "SENS10") (pin "1") (pinfunction "1_1") (pintype "passive"))
      (node (ref "SENS11") (pin "1") (pinfunction "1_1") (pintype "passive"))
      (node (ref "SENS12") (pin "1") (pinfunction "1_1") (pintype "passive"))
      (node (ref "SENS13") (pin "1") (pinfunction "1_1") (pintype "passive"))
      (node (ref "SENS14") (pin "1") (pinfunction "1_1") (pintype "passive"))
      (node (ref "SENS15") (pin "1") (pinfunction "1_1") (pintype "passive"))
      (node (ref "SENS2") (pin "1") (pinfunction "1_1") (pintype "passive"))
      (node (ref "SENS3") (pin "1") (pinfunction "1_1") (pintype "passive"))
      (node (ref "SENS4") (pin "1") (pinfunction "1_1") (pintype "passive"))
      (node (ref "SENS5") (pin "1") (pinfunction "1_1") (pintype "passive"))
      (node (ref "SENS6") (pin "1") (pinfunction "1_1") (pintype "passive"))
      (node (ref "SENS7") (pin "1") (pinfunction "1_1") (pintype "passive"))
      (node (ref "SENS8") (pin "1") (pinfunction "1_1") (pintype "passive"))
      (node (ref "SENS9") (pin "1") (pinfunction "1_1") (pintype "passive"))
      (node (ref "U1") (pin "35") (pinfunction "IO18_35") (pintype "bidirectional"))
    )
    (net (code "32") (name "GND") (class "Default")
      (node (ref "C1") (pin "2") (pinfunction "2_2") (pintype "passive"))
      (node (ref "C10") (pin "1") (pinfunction "1_1") (pintype "passive"))
      (node (ref "C11") (pin "2") (pinfunction "2_2") (pintype "passive"))
      (node (ref "C12") (pin "1") (pinfunction "1_1") (pintype "passive"))
      (node (ref "C13") (pin "1") (pinfunction "1_1") (pintype "passive"))
      (node (ref "C2") (pin "1") (pinfunction "1_1") (pintype "passive"))
      (node (ref "C3") (pin "2") (pinfunction "2_2") (pintype "passive"))
      (node (ref "C4") (pin "2") (pinfunction "2_2") (pintype "passive"))
      (node (ref "C5") (pin "2") (pinfunction "2_2") (pintype "passive"))
      (node (ref "C6") (pin "2") (pinfunction "2_2") (pintype "passive"))
      (node (ref "C7") (pin "1") (pinfunction "1_1") (pintype "passive"))
      (node (ref "C8") (pin "1") (pinfunction "1_1") (pintype "passive"))
      (node (ref "C9") (pin "2") (pinfunction "2_2") (pintype "passive"))
      (node (ref "GND") (pin "1") (pinfunction "Input_1") (pintype "passive"))
      (node (ref "H2") (pin "09") (pinfunction "09_09") (pintype "passive"))
      (node (ref "H2") (pin "14") (pinfunction "14_14") (pintype "passive"))
      (node (ref "H2") (pin "17") (pinfunction "17_17") (pintype "passive"))
      (node (ref "H2") (pin "21") (pinfunction "21_21") (pintype "passive"))
      (node (ref "H2") (pin "22") (pinfunction "22_22") (pintype "passive"))
      (node (ref "H2") (pin "29") (pinfunction "29_29") (pintype "passive"))
      (node (ref "H2") (pin "30") (pinfunction "30_30") (pintype "passive"))
      (node (ref "H2") (pin "32") (pinfunction "32_32") (pintype "passive"))
      (node (ref "H2") (pin "47") (pinfunction "47_47") (pintype "passive"))
      (node (ref "H3") (pin "A1_B12") (pinfunction "GND_A1_B12") (pintype "power_in"))
      (node (ref "H3") (pin "B1_A12") (pinfunction "GND_B1_A12") (pintype "power_in"))
      (node (ref "H3") (pin "S1") (pinfunction "SHD_S1") (pintype "power_in"))
      (node (ref "H3") (pin "S2") (pinfunction "SHD_S2") (pintype "power_in"))
      (node (ref "H3") (pin "S3") (pinfunction "SHD_S3") (pintype "power_in"))
      (node (ref "H3") (pin "S4") (pinfunction "SHD_S4") (pintype "power_in"))
      (node (ref "HEATER") (pin "2") (pinfunction "2_2") (pintype "passive"))
      (node (ref "R1") (pin "1") (pinfunction "1_1") (pintype "passive"))
      (node (ref "R10") (pin "2") (pinfunction "2_2") (pintype "passive"))
      (node (ref "R15") (pin "1") (pinfunction "1_1") (pintype "passive"))
      (node (ref "R16") (pin "1") (pinfunction "1_1") (pintype "passive"))
      (node (ref "R17") (pin "1") (pinfunction "1_1") (pintype "passive"))
      (node (ref "R18") (pin "1") (pinfunction "1_1") (pintype "passive"))
      (node (ref "R19") (pin "1") (pinfunction "1_1") (pintype "passive"))
      (node (ref "R2") (pin "1") (pinfunction "1_1") (pintype "passive"))
      (node (ref "R20") (pin "1") (pinfunction "1_1") (pintype "passive"))
      (node (ref "R21") (pin "1") (pinfunction "1_1") (pintype "passive"))
      (node (ref "R22") (pin "1") (pinfunction "1_1") (pintype "passive"))
      (node (ref "R23") (pin "1") (pinfunction "1_1") (pintype "passive"))
      (node (ref "R24") (pin "1") (pinfunction "1_1") (pintype "passive"))
      (node (ref "R25") (pin "1") (pinfunction "1_1") (pintype "passive"))
      (node (ref "R26") (pin "1") (pinfunction "1_1") (pintype "passive"))
      (node (ref "R27") (pin "1") (pinfunction "1_1") (pintype "passive"))
      (node (ref "R28") (pin "1") (pinfunction "1_1") (pintype "passive"))
      (node (ref "R29") (pin "1") (pinfunction "1_1") (pintype "passive"))
      (node (ref "R30") (pin "1") (pinfunction "1_1") (pintype "passive"))
      (node (ref "R5") (pin "1") (pinfunction "1_1") (pintype "passive"))
      (node (ref "R8") (pin "2") (pinfunction "2_2") (pintype "passive"))
      (node (ref "R9") (pin "2") (pinfunction "2_2") (pintype "passive"))
      (node (ref "U1") (pin "49") (pinfunction "GND_49") (pintype "power_in"))
      (node (ref "U2") (pin "29") (pinfunction "GND_29") (pintype "power_in"))
      (node (ref "U2") (pin "3") (pinfunction "GND_3") (pintype "power_in"))
      (node (ref "U3") (pin "2") (pinfunction "GND_2") (pintype "power_in"))
      (node (ref "U4") (pin "2") (pinfunction "GND_2") (pintype "power_in"))
      (node (ref "U5") (pin "2") (pinfunction "C_2") (pintype "passive"))
    )
    (net (code "33") (name "Net-(D2-Cathode)") (class "Default")
      (node (ref "D2") (pin "1") (pinfunction "Cathode_1") (pintype "passive"))
      (node (ref "R8") (pin "1") (pinfunction "1_1") (pintype "passive"))
    )
    (net (code "34") (name "Net-(D3-Cathode)") (class "Default")
      (node (ref "D3") (pin "1") (pinfunction "Cathode_1") (pintype "passive"))
      (node (ref "R9") (pin "1") (pinfunction "1_1") (pintype "passive"))
    )
    (net (code "35") (name "Net-(D4-Cathode)") (class "Default")
      (node (ref "D4") (pin "1") (pinfunction "Cathode_1") (pintype "passive"))
      (node (ref "R10") (pin "1") (pinfunction "1_1") (pintype "passive"))
    )
    (net (code "36") (name "Net-(H3-CC1)") (class "Default")
      (node (ref "H3") (pin "A5") (pinfunction "CC1_A5") (pintype "passive"))
      (node (ref "R1") (pin "2") (pinfunction "2_2") (pintype "passive"))
    )
    (net (code "37") (name "Net-(H3-CC2)") (class "Default")
      (node (ref "H3") (pin "B5") (pinfunction "CC2_B5") (pintype "passive"))
      (node (ref "R2") (pin "2") (pinfunction "2_2") (pintype "passive"))
    )
    (net (code "38") (name "Net-(Q2A-G)") (class "Default")
      (node (ref "Q2") (pin "2") (pinfunction "G_2") (pintype "passive"))
      (node (ref "R6") (pin "2") (pinfunction "2_2") (pintype "passive"))
    )
    (net (code "39") (name "Net-(Q2B-G)") (class "Default")
      (node (ref "Q2") (pin "5") (pinfunction "G_5") (pintype "passive"))
      (node (ref "R7") (pin "2") (pinfunction "2_2") (pintype "passive"))
    )
    (net (code "40") (name "Net-(U2-RSTb)") (class "Default")
      (node (ref "R3") (pin "1") (pinfunction "1_1") (pintype "passive"))
      (node (ref "U2") (pin "9") (pinfunction "RSTb_9") (pintype "input"))
    )
    (net (code "41") (name "Net-(U2-VBUS)") (class "Default")
      (node (ref "R4") (pin "1") (pinfunction "1_1") (pintype "passive"))
      (node (ref "R5") (pin "2") (pinfunction "2_2") (pintype "passive"))
      (node (ref "U2") (pin "8") (pinfunction "VBUS_8") (pintype "power_in"))
    )
    (net (code "42") (name "Net-(U5-2_DRAIN)") (class "Default")
      (node (ref "R14") (pin "1") (pinfunction "1_1") (pintype "passive"))
      (node (ref "U5") (pin "4") (pinfunction "2_DRAIN_4") (pintype "passive"))
    )
    (net (code "43") (name "Net-(U5-A)") (class "Default")
      (node (ref "R13") (pin "2") (pinfunction "2_2") (pintype "passive"))
      (node (ref "U5") (pin "1") (pinfunction "A_1") (pintype "passive"))
    )
    (net (code "44") (name "VBUS") (class "Default")
      (node (ref "C2") (pin "2") (pinfunction "2_2") (pintype "passive"))
      (node (ref "D1") (pin "2") (pinfunction "Anode_2") (pintype "passive"))
      (node (ref "D3") (pin "2") (pinfunction "Anode_2") (pintype "passive"))
      (node (ref "H2") (pin "13") (pinfunction "13_13") (pintype "passive"))
      (node (ref "Q1") (pin "1") (pinfunction "G_1") (pintype "passive"))
      (node (ref "R14") (pin "2") (pinfunction "2_2") (pintype "passive"))
      (node (ref "VBUS") (pin "1") (pinfunction "Input_1") (pintype "passive"))
    )
    (net (code "45") (name "VUSB") (class "Default")
      (node (ref "C1") (pin "1") (pinfunction "1_1") (pintype "passive"))
      (node (ref "D2") (pin "2") (pinfunction "Anode_2") (pintype "passive"))
      (node (ref "H3") (pin "A4_B9") (pinfunction "VBUS_A4_B9") (pintype "power_in"))
      (node (ref "H3") (pin "B4_A9") (pinfunction "VBUS_B4_A9") (pintype "power_in"))
      (node (ref "Q1") (pin "3") (pinfunction "D_3") (pintype "passive"))
      (node (ref "R3") (pin "2") (pinfunction "2_2") (pintype "passive"))
      (node (ref "R4") (pin "2") (pinfunction "2_2") (pintype "passive"))
      (node (ref "U2") (pin "6") (pinfunction "VDD_6") (pintype "power_in"))
      (node (ref "U2") (pin "7") (pinfunction "VREGIN_7") (pintype "power_in"))
      (node (ref "U4") (pin "1") (pinfunction "L1_1") (pintype "passive"))
      (node (ref "VUSB") (pin "1") (pinfunction "Input_1") (pintype "passive"))
    )
    (net (code "46") (name "unconnected-(H1-Pad01)") (class "Default")
      (node (ref "H1") (pin "01") (pinfunction "01_01") (pintype "passive+no_connect"))
    )
    (net (code "47") (name "unconnected-(H1-Pad02)") (class "Default")
      (node (ref "H1") (pin "02") (pinfunction "02_02") (pintype "passive+no_connect"))
    )
    (net (code "48") (name "unconnected-(H1-Pad03)") (class "Default")
      (node (ref "H1") (pin "03") (pinfunction "03_03") (pintype "passive+no_connect"))
    )
    (net (code "49") (name "unconnected-(H1-Pad04)") (class "Default")
      (node (ref "H1") (pin "04") (pinfunction "04_04") (pintype "passive+no_connect"))
    )
    (net (code "50") (name "unconnected-(H1-Pad05)") (class "Default")
      (node (ref "H1") (pin "05") (pinfunction "05_05") (pintype "passive+no_connect"))
    )
    (net (code "51") (name "unconnected-(H1-Pad06)") (class "Default")
      (node (ref "H1") (pin "06") (pinfunction "06_06") (pintype "passive+no_connect"))
    )
    (net (code "52") (name "unconnected-(H1-Pad07)") (class "Default")
      (node (ref "H1") (pin "07") (pinfunction "07_07") (pintype "passive+no_connect"))
    )
    (net (code "53") (name "unconnected-(H1-Pad08)") (class "Default")
      (node (ref "H1") (pin "08") (pinfunction "08_08") (pintype "passive+no_connect"))
    )
    (net (code "54") (name "unconnected-(H1-Pad09)") (class "Default")
      (node (ref "H1") (pin "09") (pinfunction "09_09") (pintype "passive+no_connect"))
    )
    (net (code "55") (name "unconnected-(H1-Pad10)") (class "Default")
      (node (ref "H1") (pin "10") (pinfunction "10_10") (pintype "passive+no_connect"))
    )
    (net (code "56") (name "unconnected-(H1-Pad11)") (class "Default")
      (node (ref "H1") (pin "11") (pinfunction "11_11") (pintype "passive+no_connect"))
    )
    (net (code "57") (name "unconnected-(H1-Pad12)") (class "Default")
      (node (ref "H1") (pin "12") (pinfunction "12_12") (pintype "passive"))
    )
    (net (code "58") (name "unconnected-(H1-Pad13)") (class "Default")
      (node (ref "H1") (pin "13") (pinfunction "13_13") (pintype "passive+no_connect"))
    )
    (net (code "59") (name "unconnected-(H1-Pad14)") (class "Default")
      (node (ref "H1") (pin "14") (pinfunction "14_14") (pintype "passive+no_connect"))
    )
    (net (code "60") (name "unconnected-(H1-Pad15)") (class "Default")
      (node (ref "H1") (pin "15") (pinfunction "15_15") (pintype "passive+no_connect"))
    )
    (net (code "61") (name "unconnected-(H1-Pad16)") (class "Default")
      (node (ref "H1") (pin "16") (pinfunction "16_16") (pintype "passive+no_connect"))
    )
    (net (code "62") (name "unconnected-(H1-Pad17)") (class "Default")
      (node (ref "H1") (pin "17") (pinfunction "17_17") (pintype "passive+no_connect"))
    )
    (net (code "63") (name "unconnected-(H1-Pad18)") (class "Default")
      (node (ref "H1") (pin "18") (pinfunction "18_18") (pintype "passive+no_connect"))
    )
    (net (code "64") (name "unconnected-(H1-Pad19)") (class "Default")
      (node (ref "H1") (pin "19") (pinfunction "19_19") (pintype "passive+no_connect"))
    )
    (net (code "65") (name "unconnected-(H1-Pad20)") (class "Default")
      (node (ref "H1") (pin "20") (pinfunction "20_20") (pintype "passive+no_connect"))
    )
    (net (code "66") (name "unconnected-(H1-Pad21)") (class "Default")
      (node (ref "H1") (pin "21") (pinfunction "21_21") (pintype "passive+no_connect"))
    )
    (net (code "67") (name "unconnected-(H1-Pad22)") (class "Default")
      (node (ref "H1") (pin "22") (pinfunction "22_22") (pintype "passive+no_connect"))
    )
    (net (code "68") (name "unconnected-(H1-Pad23)") (class "Default")
      (node (ref "H1") (pin "23") (pinfunction "23_23") (pintype "passive+no_connect"))
    )
    (net (code "69") (name "unconnected-(H1-Pad24)") (class "Default")
      (node (ref "H1") (pin "24") (pinfunction "24_24") (pintype "passive+no_connect"))
    )
    (net (code "70") (name "unconnected-(H1-Pad25)") (class "Default")
      (node (ref "H1") (pin "25") (pinfunction "25_25") (pintype "passive+no_connect"))
    )
    (net (code "71") (name "unconnected-(H1-Pad26)") (class "Default")
      (node (ref "H1") (pin "26") (pinfunction "26_26") (pintype "passive+no_connect"))
    )
    (net (code "72") (name "unconnected-(H1-Pad27)") (class "Default")
      (node (ref "H1") (pin "27") (pinfunction "27_27") (pintype "passive+no_connect"))
    )
    (net (code "73") (name "unconnected-(H1-Pad28)") (class "Default")
      (node (ref "H1") (pin "28") (pinfunction "28_28") (pintype "passive+no_connect"))
    )
    (net (code "74") (name "unconnected-(H1-Pad29)") (class "Default")
      (node (ref "H1") (pin "29") (pinfunction "29_29") (pintype "passive+no_connect"))
    )
    (net (code "75") (name "unconnected-(H1-Pad30)") (class "Default")
      (node (ref "H1") (pin "30") (pinfunction "30_30") (pintype "passive+no_connect"))
    )
    (net (code "76") (name "unconnected-(H1-Pad31)") (class "Default")
      (node (ref "H1") (pin "31") (pinfunction "31_31") (pintype "passive+no_connect"))
    )
    (net (code "77") (name "unconnected-(H1-Pad32)") (class "Default")
      (node (ref "H1") (pin "32") (pinfunction "32_32") (pintype "passive+no_connect"))
    )
    (net (code "78") (name "unconnected-(H1-Pad33)") (class "Default")
      (node (ref "H1") (pin "33") (pinfunction "33_33") (pintype "passive+no_connect"))
    )
    (net (code "79") (name "unconnected-(H1-Pad34)") (class "Default")
      (node (ref "H1") (pin "34") (pinfunction "34_34") (pintype "passive+no_connect"))
    )
    (net (code "80") (name "unconnected-(H1-Pad35)") (class "Default")
      (node (ref "H1") (pin "35") (pinfunction "35_35") (pintype "passive+no_connect"))
    )
    (net (code "81") (name "unconnected-(H1-Pad36)") (class "Default")
      (node (ref "H1") (pin "36") (pinfunction "36_36") (pintype "passive+no_connect"))
    )
    (net (code "82") (name "unconnected-(H1-Pad37)") (class "Default")
      (node (ref "H1") (pin "37") (pinfunction "37_37") (pintype "passive+no_connect"))
    )
    (net (code "83") (name "unconnected-(H1-Pad38)") (class "Default")
      (node (ref "H1") (pin "38") (pinfunction "38_38") (pintype "passive+no_connect"))
    )
    (net (code "84") (name "unconnected-(H1-Pad39)") (class "Default")
      (node (ref "H1") (pin "39") (pinfunction "39_39") (pintype "passive+no_connect"))
    )
    (net (code "85") (name "unconnected-(H1-Pad40)") (class "Default")
      (node (ref "H1") (pin "40") (pinfunction "40_40") (pintype "passive+no_connect"))
    )
    (net (code "86") (name "unconnected-(H1-Pad42)") (class "Default")
      (node (ref "H1") (pin "42") (pinfunction "42_42") (pintype "passive+no_connect"))
    )
    (net (code "87") (name "unconnected-(H1-Pad44)") (class "Default")
      (node (ref "H1") (pin "44") (pinfunction "44_44") (pintype "passive+no_connect"))
    )
    (net (code "88") (name "unconnected-(H1-Pad45)") (class "Default")
      (node (ref "H1") (pin "45") (pinfunction "45_45") (pintype "passive+no_connect"))
    )
    (net (code "89") (name "unconnected-(H1-Pad46)") (class "Default")
      (node (ref "H1") (pin "46") (pinfunction "46_46") (pintype "passive+no_connect"))
    )
    (net (code "90") (name "unconnected-(H1-Pad47)") (class "Default")
      (node (ref "H1") (pin "47") (pinfunction "47_47") (pintype "passive+no_connect"))
    )
    (net (code "91") (name "unconnected-(H1-Pad48)") (class "Default")
      (node (ref "H1") (pin "48") (pinfunction "48_48") (pintype "passive+no_connect"))
    )
    (net (code "92") (name "unconnected-(H1-Pad49)") (class "Default")
      (node (ref "H1") (pin "49") (pinfunction "49_49") (pintype "passive+no_connect"))
    )
    (net (code "93") (name "unconnected-(H1-Pad50)") (class "Default")
      (node (ref "H1") (pin "50") (pinfunction "50_50") (pintype "passive+no_connect"))
    )
    (net (code "94") (name "unconnected-(H1-Pad51)") (class "Default")
      (node (ref "H1") (pin "51") (pinfunction "51_51") (pintype "passive+no_connect"))
    )
    (net (code "95") (name "unconnected-(H1-Pad52)") (class "Default")
      (node (ref "H1") (pin "52") (pinfunction "52_52") (pintype "passive+no_connect"))
    )
    (net (code "96") (name "unconnected-(H2-Pad01)") (class "Default")
      (node (ref "H2") (pin "01") (pinfunction "01_01") (pintype "passive+no_connect"))
    )
    (net (code "97") (name "unconnected-(H2-Pad02)") (class "Default")
      (node (ref "H2") (pin "02") (pinfunction "02_02") (pintype "passive+no_connect"))
    )
    (net (code "98") (name "unconnected-(H2-Pad03)") (class "Default")
      (node (ref "H2") (pin "03") (pinfunction "03_03") (pintype "passive+no_connect"))
    )
    (net (code "99") (name "unconnected-(H2-Pad04)") (class "Default")
      (node (ref "H2") (pin "04") (pinfunction "04_04") (pintype "passive+no_connect"))
    )
    (net (code "100") (name "unconnected-(H2-Pad05)") (class "Default")
      (node (ref "H2") (pin "05") (pinfunction "05_05") (pintype "passive+no_connect"))
    )
    (net (code "101") (name "unconnected-(H2-Pad06)") (class "Default")
      (node (ref "H2") (pin "06") (pinfunction "06_06") (pintype "passive+no_connect"))
    )
    (net (code "102") (name "unconnected-(H2-Pad07)") (class "Default")
      (node (ref "H2") (pin "07") (pinfunction "07_07") (pintype "passive+no_connect"))
    )
    (net (code "103") (name "unconnected-(H2-Pad08)") (class "Default")
      (node (ref "H2") (pin "08") (pinfunction "08_08") (pintype "passive+no_connect"))
    )
    (net (code "104") (name "unconnected-(H2-Pad10)") (class "Default")
      (node (ref "H2") (pin "10") (pinfunction "10_10") (pintype "passive+no_connect"))
    )
    (net (code "105") (name "unconnected-(H2-Pad11)") (class "Default")
      (node (ref "H2") (pin "11") (pinfunction "11_11") (pintype "passive+no_connect"))
    )
    (net (code "106") (name "unconnected-(H2-Pad12)") (class "Default")
      (node (ref "H2") (pin "12") (pinfunction "12_12") (pintype "passive+no_connect"))
    )
    (net (code "107") (name "unconnected-(H2-Pad15)") (class "Default")
      (node (ref "H2") (pin "15") (pinfunction "15_15") (pintype "passive+no_connect"))
    )
    (net (code "108") (name "unconnected-(H2-Pad16)") (class "Default")
      (node (ref "H2") (pin "16") (pinfunction "16_16") (pintype "passive+no_connect"))
    )
    (net (code "109") (name "unconnected-(H2-Pad18)") (class "Default")
      (node (ref "H2") (pin "18") (pinfunction "18_18") (pintype "passive+no_connect"))
    )
    (net (code "110") (name "unconnected-(H2-Pad19)") (class "Default")
      (node (ref "H2") (pin "19") (pinfunction "19_19") (pintype "passive+no_connect"))
    )
    (net (code "111") (name "unconnected-(H2-Pad20)") (class "Default")
      (node (ref "H2") (pin "20") (pinfunction "20_20") (pintype "passive+no_connect"))
    )
    (net (code "112") (name "unconnected-(H2-Pad23)") (class "Default")
      (node (ref "H2") (pin "23") (pinfunction "23_23") (pintype "passive+no_connect"))
    )
    (net (code "113") (name "unconnected-(H2-Pad24)") (class "Default")
      (node (ref "H2") (pin "24") (pinfunction "24_24") (pintype "passive+no_connect"))
    )
    (net (code "114") (name "unconnected-(H2-Pad25)") (class "Default")
      (node (ref "H2") (pin "25") (pinfunction "25_25") (pintype "passive+no_connect"))
    )
    (net (code "115") (name "unconnected-(H2-Pad26)") (class "Default")
      (node (ref "H2") (pin "26") (pinfunction "26_26") (pintype "passive+no_connect"))
    )
    (net (code "116") (name "unconnected-(H2-Pad27)") (class "Default")
      (node (ref "H2") (pin "27") (pinfunction "27_27") (pintype "passive+no_connect"))
    )
    (net (code "117") (name "unconnected-(H2-Pad28)") (class "Default")
      (node (ref "H2") (pin "28") (pinfunction "28_28") (pintype "passive+no_connect"))
    )
    (net (code "118") (name "unconnected-(H2-Pad31)") (class "Default")
      (node (ref "H2") (pin "31") (pinfunction "31_31") (pintype "passive+no_connect"))
    )
    (net (code "119") (name "unconnected-(H2-Pad33)") (class "Default")
      (node (ref "H2") (pin "33") (pinfunction "33_33") (pintype "passive+no_connect"))
    )
    (net (code "120") (name "unconnected-(H2-Pad34)") (class "Default")
      (node (ref "H2") (pin "34") (pinfunction "34_34") (pintype "passive+no_connect"))
    )
    (net (code "121") (name "unconnected-(H2-Pad35)") (class "Default")
      (node (ref "H2") (pin "35") (pinfunction "35_35") (pintype "passive+no_connect"))
    )
    (net (code "122") (name "unconnected-(H2-Pad36)") (class "Default")
      (node (ref "H2") (pin "36") (pinfunction "36_36") (pintype "passive+no_connect"))
    )
    (net (code "123") (name "unconnected-(H2-Pad37)") (class "Default")
      (node (ref "H2") (pin "37") (pinfunction "37_37") (pintype "passive+no_connect"))
    )
    (net (code "124") (name "unconnected-(H2-Pad38)") (class "Default")
      (node (ref "H2") (pin "38") (pinfunction "38_38") (pintype "passive+no_connect"))
    )
    (net (code "125") (name "unconnected-(H2-Pad39)") (class "Default")
      (node (ref "H2") (pin "39") (pinfunction "39_39") (pintype "passive+no_connect"))
    )
    (net (code "126") (name "unconnected-(H2-Pad40)") (class "Default")
      (node (ref "H2") (pin "40") (pinfunction "40_40") (pintype "passive+no_connect"))
    )
    (net (code "127") (name "unconnected-(H2-Pad41)") (class "Default")
      (node (ref "H2") (pin "41") (pinfunction "41_41") (pintype "passive+no_connect"))
    )
    (net (code "128") (name "unconnected-(H2-Pad42)") (class "Default")
      (node (ref "H2") (pin "42") (pinfunction "42_42") (pintype "passive+no_connect"))
    )
    (net (code "129") (name "unconnected-(H2-Pad43)") (class "Default")
      (node (ref "H2") (pin "43") (pinfunction "43_43") (pintype "passive+no_connect"))
    )
    (net (code "130") (name "unconnected-(H2-Pad44)") (class "Default")
      (node (ref "H2") (pin "44") (pinfunction "44_44") (pintype "passive+no_connect"))
    )
    (net (code "131") (name "unconnected-(H2-Pad45)") (class "Default")
      (node (ref "H2") (pin "45") (pinfunction "45_45") (pintype "passive+no_connect"))
    )
    (net (code "132") (name "unconnected-(H2-Pad46)") (class "Default")
      (node (ref "H2") (pin "46") (pinfunction "46_46") (pintype "passive+no_connect"))
    )
    (net (code "133") (name "unconnected-(H2-Pad48)") (class "Default")
      (node (ref "H2") (pin "48") (pinfunction "48_48") (pintype "passive+no_connect"))
    )
    (net (code "134") (name "unconnected-(H2-Pad49)") (class "Default")
      (node (ref "H2") (pin "49") (pinfunction "49_49") (pintype "passive+no_connect"))
    )
    (net (code "135") (name "unconnected-(H2-Pad50)") (class "Default")
      (node (ref "H2") (pin "50") (pinfunction "50_50") (pintype "passive+no_connect"))
    )
    (net (code "136") (name "unconnected-(H2-Pad51)") (class "Default")
      (node (ref "H2") (pin "51") (pinfunction "51_51") (pintype "passive+no_connect"))
    )
    (net (code "137") (name "unconnected-(H2-Pad52)") (class "Default")
      (node (ref "H2") (pin "52") (pinfunction "52_52") (pintype "passive+no_connect"))
    )
    (net (code "138") (name "unconnected-(H3-SBU1-PadA8)") (class "Default")
      (node (ref "H3") (pin "A8") (pinfunction "SBU1_A8") (pintype "power_in+no_connect"))
    )
    (net (code "139") (name "unconnected-(H3-SBU2-PadB8)") (class "Default")
      (node (ref "H3") (pin "B8") (pinfunction "SBU2_B8") (pintype "power_in+no_connect"))
    )
    (net (code "140") (name "unconnected-(U1-CAP1_NC-Pad48)") (class "Default")
      (node (ref "U1") (pin "48") (pinfunction "CAP1_NC_48") (pintype "passive+no_connect"))
    )
    (net (code "141") (name "unconnected-(U1-CAP2_NC-Pad47)") (class "Default")
      (node (ref "U1") (pin "47") (pinfunction "CAP2_NC_47") (pintype "passive+no_connect"))
    )
    (net (code "142") (name "unconnected-(U1-CLK-Pad31)") (class "Default")
      (node (ref "U1") (pin "31") (pinfunction "CLK_31") (pintype "bidirectional+no_connect"))
    )
    (net (code "143") (name "unconnected-(U1-CMD-Pad30)") (class "Default")
      (node (ref "U1") (pin "30") (pinfunction "CMD_30") (pintype "bidirectional+no_connect"))
    )
    (net (code "144") (name "unconnected-(U1-IO2-Pad22)") (class "Default")
      (node (ref "U1") (pin "22") (pinfunction "IO2_22") (pintype "bidirectional+no_connect"))
    )
    (net (code "145") (name "unconnected-(U1-IO15-Pad21)") (class "Default")
      (node (ref "U1") (pin "21") (pinfunction "IO15_21") (pintype "bidirectional+no_connect"))
    )
    (net (code "146") (name "unconnected-(U1-IO16-Pad25)") (class "Default")
      (node (ref "U1") (pin "25") (pinfunction "IO16_25") (pintype "bidirectional+no_connect"))
    )
    (net (code "147") (name "unconnected-(U1-IO17-Pad27)") (class "Default")
      (node (ref "U1") (pin "27") (pinfunction "IO17_27") (pintype "bidirectional+no_connect"))
    )
    (net (code "148") (name "unconnected-(U1-IO23-Pad36)") (class "Default")
      (node (ref "U1") (pin "36") (pinfunction "IO23_36") (pintype "bidirectional+no_connect"))
    )
    (net (code "149") (name "unconnected-(U1-LNA_IN-Pad2)") (class "Default")
      (node (ref "U1") (pin "2") (pinfunction "LNA_IN_2") (pintype "bidirectional+no_connect"))
    )
    (net (code "150") (name "unconnected-(U1-SD0-Pad32)") (class "Default")
      (node (ref "U1") (pin "32") (pinfunction "SD0_32") (pintype "bidirectional+no_connect"))
    )
    (net (code "151") (name "unconnected-(U1-SD1-Pad33)") (class "Default")
      (node (ref "U1") (pin "33") (pinfunction "SD1_33") (pintype "bidirectional+no_connect"))
    )
    (net (code "152") (name "unconnected-(U1-SD2-Pad28)") (class "Default")
      (node (ref "U1") (pin "28") (pinfunction "SD2_28") (pintype "bidirectional+no_connect"))
    )
    (net (code "153") (name "unconnected-(U1-SD3-Pad29)") (class "Default")
      (node (ref "U1") (pin "29") (pinfunction "SD3_29") (pintype "bidirectional+no_connect"))
    )
    (net (code "154") (name "unconnected-(U1-VDD_SDIO-Pad26)") (class "Default")
      (node (ref "U1") (pin "26") (pinfunction "VDD_SDIO_26") (pintype "bidirectional+no_connect"))
    )
    (net (code "155") (name "unconnected-(U1-XTAL_N_NC-Pad44)") (class "Default")
      (node (ref "U1") (pin "44") (pinfunction "XTAL_N_NC_44") (pintype "passive+no_connect"))
    )
    (net (code "156") (name "unconnected-(U1-XTAL_P_NC-Pad45)") (class "Default")
      (node (ref "U1") (pin "45") (pinfunction "XTAL_P_NC_45") (pintype "passive+no_connect"))
    )
    (net (code "157") (name "unconnected-(U2-CHR0-Pad15)") (class "Default")
      (node (ref "U2") (pin "15") (pinfunction "CHR0_15") (pintype "output+no_connect"))
    )
    (net (code "158") (name "unconnected-(U2-CHR1-Pad14)") (class "Default")
      (node (ref "U2") (pin "14") (pinfunction "CHR1_14") (pintype "output+no_connect"))
    )
    (net (code "159") (name "unconnected-(U2-CHREN-Pad13)") (class "Default")
      (node (ref "U2") (pin "13") (pinfunction "CHREN_13") (pintype "output+no_connect"))
    )
    (net (code "160") (name "unconnected-(U2-CTS-Pad23)") (class "Default")
      (node (ref "U2") (pin "23") (pinfunction "CTS_23") (pintype "input+no_connect"))
    )
    (net (code "161") (name "unconnected-(U2-DCD-Pad1)") (class "Default")
      (node (ref "U2") (pin "1") (pinfunction "DCD_1") (pintype "input+no_connect"))
    )
    (net (code "162") (name "unconnected-(U2-DSR-Pad27)") (class "Default")
      (node (ref "U2") (pin "27") (pinfunction "DSR_27") (pintype "input+no_connect"))
    )
    (net (code "163") (name "unconnected-(U2-GPIO.0_{slash}_TXT-Pad19)") (class "Default")
      (node (ref "U2") (pin "19") (pinfunction "GPIO.0_/_TXT_19") (pintype "bidirectional+no_connect"))
    )
    (net (code "164") (name "unconnected-(U2-GPIO.1_{slash}_RXT-Pad18)") (class "Default")
      (node (ref "U2") (pin "18") (pinfunction "GPIO.1_/_RXT_18") (pintype "bidirectional+no_connect"))
    )
    (net (code "165") (name "unconnected-(U2-GPIO.2_{slash}_RS485-Pad17)") (class "Default")
      (node (ref "U2") (pin "17") (pinfunction "GPIO.2_/_RS485_17") (pintype "bidirectional+no_connect"))
    )
    (net (code "166") (name "unconnected-(U2-GPIO.3_{slash}_WAKEUP-Pad16)") (class "Default")
      (node (ref "U2") (pin "16") (pinfunction "GPIO.3_/_WAKEUP_16") (pintype "bidirectional+no_connect"))
    )
    (net (code "167") (name "unconnected-(U2-GPIO.4-Pad22)") (class "Default")
      (node (ref "U2") (pin "22") (pinfunction "GPIO.4_22") (pintype "bidirectional+no_connect"))
    )
    (net (code "168") (name "unconnected-(U2-GPIO.5-Pad21)") (class "Default")
      (node (ref "U2") (pin "21") (pinfunction "GPIO.5_21") (pintype "bidirectional+no_connect"))
    )
    (net (code "169") (name "unconnected-(U2-GPIO.6-Pad20)") (class "Default")
      (node (ref "U2") (pin "20") (pinfunction "GPIO.6_20") (pintype "bidirectional+no_connect"))
    )
    (net (code "170") (name "unconnected-(U2-NC-Pad10)") (class "Default")
      (node (ref "U2") (pin "10") (pinfunction "NC_10") (pintype "passive+no_connect"))
    )
    (net (code "171") (name "unconnected-(U2-RI_{slash}_CLK-Pad2)") (class "Default")
      (node (ref "U2") (pin "2") (pinfunction "RI_/_CLK_2") (pintype "input+no_connect"))
    )
    (net (code "172") (name "unconnected-(U2-SUSPEND-Pad12)") (class "Default")
      (node (ref "U2") (pin "12") (pinfunction "SUSPEND_12") (pintype "output+no_connect"))
    )
    (net (code "173") (name "unconnected-(U2-SUSPENDb-Pad11)") (class "Default")
      (node (ref "U2") (pin "11") (pinfunction "SUSPENDb_11") (pintype "output+no_connect"))
    )
    (net (code "174") (name "unconnected-(U3-NC-Pad4)") (class "Default")
      (node (ref "U3") (pin "4") (pinfunction "NC_4") (pintype "passive+no_connect"))
    )
    (net (code "175") (name "unconnected-(U4-L4-Pad5)") (class "Default")
      (node (ref "U4") (pin "5") (pinfunction "L4_5") (pintype "passive+no_connect"))
    )
    (net (code "176") (name "unconnected-(U4-L5-Pad6)") (class "Default")
      (node (ref "U4") (pin "6") (pinfunction "L5_6") (pintype "passive+no_connect"))
    )
  )
)
